# Ethernet.net
KiCad netlist of a schematic drawn in Altium Designer
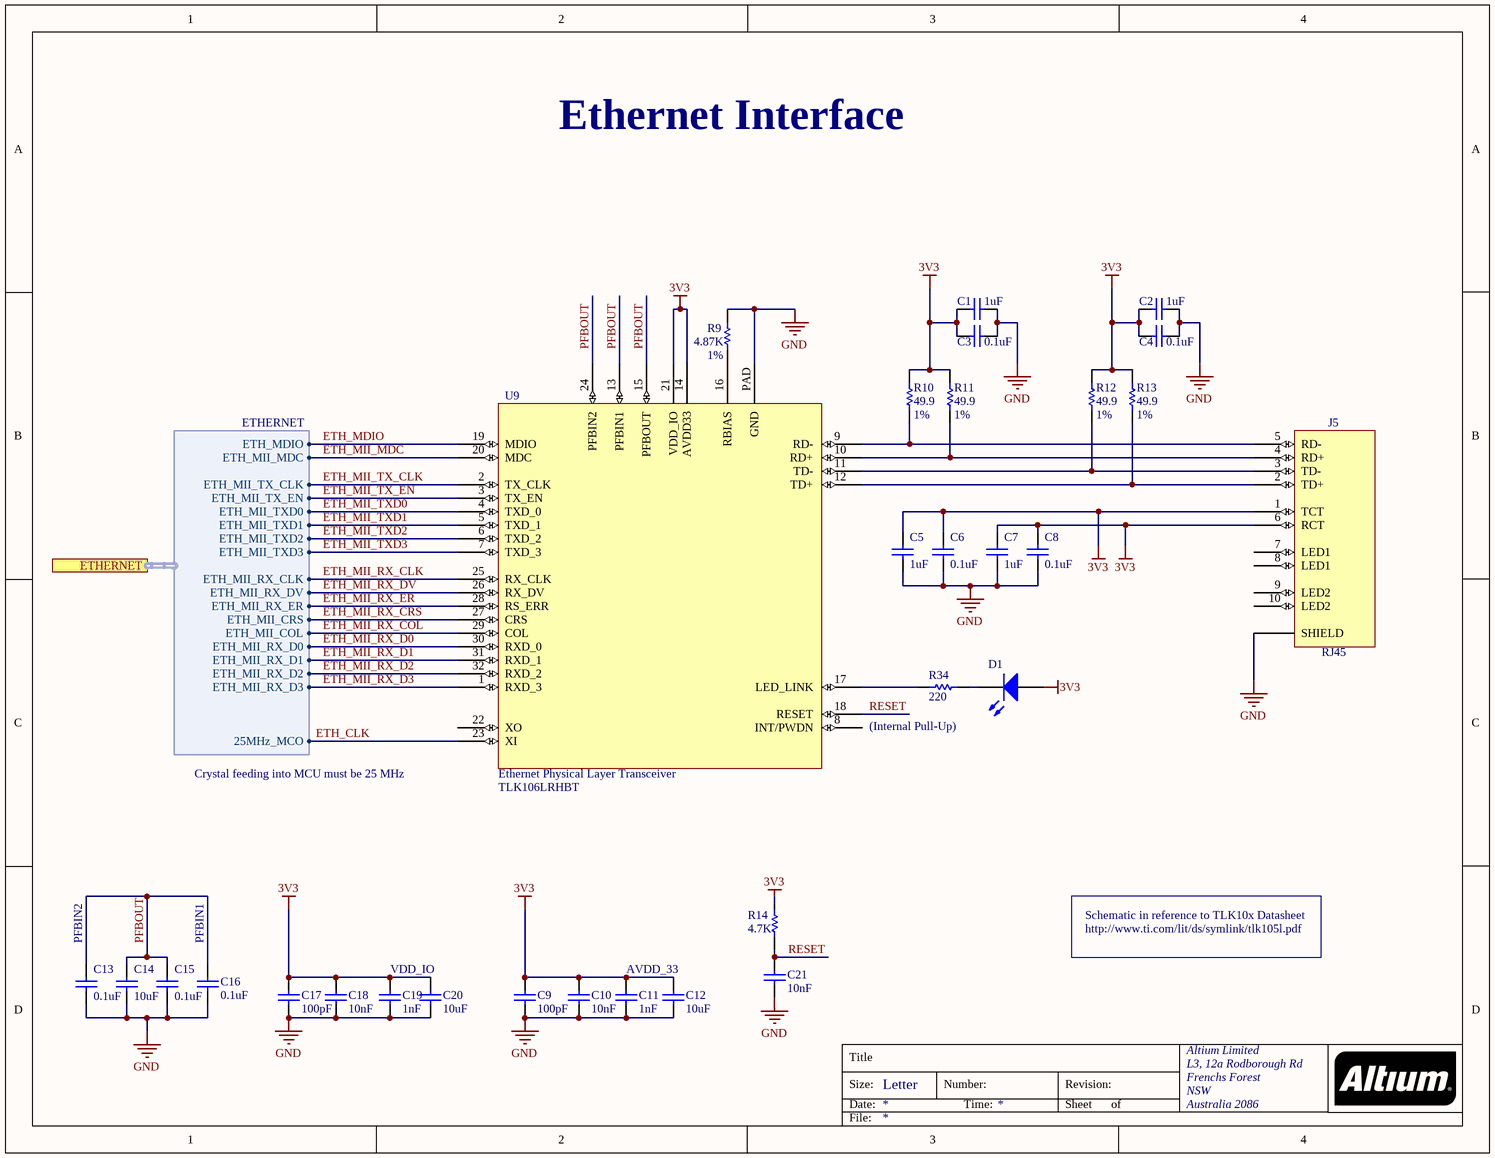
[diagram p0: Ethernet.SchDoc]

(export (version "E")
  (design (tool "Eeschema 10.0.6"))
  (components
    (comp (ref "C1")
      (value "1uF")
      (footprint "0402")
      (description "Capacitor")
      (fields (field (name "Comment") "Cap"))
      (libsource (lib "Miscellaneous Devices") (part "Cap"))
    )
    (comp (ref "C2")
      (value "1uF")
      (footprint "0402")
      (description "Capacitor")
      (fields (field (name "Comment") "Cap"))
      (libsource (lib "Miscellaneous Devices") (part "Cap"))
    )
    (comp (ref "C3")
      (value "0.1uF")
      (footprint "0402")
      (description "Capacitor")
      (fields (field (name "Comment") "Cap"))
      (libsource (lib "Miscellaneous Devices") (part "Cap"))
    )
    (comp (ref "C4")
      (value "0.1uF")
      (footprint "0402")
      (description "Capacitor")
      (fields (field (name "Comment") "Cap"))
      (libsource (lib "Miscellaneous Devices") (part "Cap"))
    )
    (comp (ref "C5")
      (value "1uF")
      (footprint "0402")
      (description "Capacitor")
      (fields (field (name "Comment") "Cap"))
      (libsource (lib "Miscellaneous Devices") (part "Cap"))
    )
    (comp (ref "C6")
      (value "0.1uF")
      (footprint "0402")
      (description "Capacitor")
      (fields (field (name "Comment") "Cap"))
      (libsource (lib "Miscellaneous Devices") (part "Cap"))
    )
    (comp (ref "C7")
      (value "1uF")
      (footprint "0402")
      (description "Capacitor")
      (fields (field (name "Comment") "Cap"))
      (libsource (lib "Miscellaneous Devices") (part "Cap"))
    )
    (comp (ref "C8")
      (value "0.1uF")
      (footprint "0402")
      (description "Capacitor")
      (fields (field (name "Comment") "Cap"))
      (libsource (lib "Miscellaneous Devices") (part "Cap"))
    )
    (comp (ref "C9")
      (value "100pF")
      (footprint "0402")
      (description "Capacitor (Semiconductor SIM Model)")
      (fields (field (name "Comment") "Cap Semi"))
      (libsource (lib "Miscellaneous Devices") (part "Cap Semi"))
    )
    (comp (ref "C10")
      (value "10nF")
      (footprint "0402")
      (description "Capacitor (Semiconductor SIM Model)")
      (fields (field (name "Comment") "Cap Semi"))
      (libsource (lib "Miscellaneous Devices") (part "Cap Semi"))
    )
    (comp (ref "C11")
      (value "1nF")
      (footprint "0402")
      (description "Capacitor (Semiconductor SIM Model)")
      (fields (field (name "Comment") "Cap Semi"))
      (libsource (lib "Miscellaneous Devices") (part "Cap Semi"))
    )
    (comp (ref "C12")
      (value "10uF")
      (footprint "0402")
      (description "Capacitor (Semiconductor SIM Model)")
      (fields (field (name "Comment") "Cap Semi"))
      (libsource (lib "Miscellaneous Devices") (part "Cap Semi"))
    )
    (comp (ref "C13")
      (value "0.1uF")
      (footprint "0402")
      (description "Capacitor (Semiconductor SIM Model)")
      (fields (field (name "Comment") "Cap Semi"))
      (libsource (lib "Miscellaneous Devices") (part "Cap Semi"))
    )
    (comp (ref "C14")
      (value "10uF")
      (footprint "0402")
      (description "Capacitor (Semiconductor SIM Model)")
      (fields (field (name "Comment") "Cap Semi"))
      (libsource (lib "Miscellaneous Devices") (part "Cap Semi"))
    )
    (comp (ref "C15")
      (value "0.1uF")
      (footprint "0402")
      (description "Capacitor (Semiconductor SIM Model)")
      (fields (field (name "Comment") "Cap Semi"))
      (libsource (lib "Miscellaneous Devices") (part "Cap Semi"))
    )
    (comp (ref "C16")
      (value "0.1uF")
      (footprint "0402")
      (description "Capacitor (Semiconductor SIM Model)")
      (fields (field (name "Comment") "Cap Semi"))
      (libsource (lib "Miscellaneous Devices") (part "Cap Semi"))
    )
    (comp (ref "C17")
      (value "100pF")
      (footprint "0402")
      (description "Capacitor (Semiconductor SIM Model)")
      (fields (field (name "Comment") "Cap Semi"))
      (libsource (lib "Miscellaneous Devices") (part "Cap Semi"))
    )
    (comp (ref "C18")
      (value "10nF")
      (footprint "0402")
      (description "Capacitor (Semiconductor SIM Model)")
      (fields (field (name "Comment") "Cap Semi"))
      (libsource (lib "Miscellaneous Devices") (part "Cap Semi"))
    )
    (comp (ref "C19")
      (value "1nF")
      (footprint "0402")
      (description "Capacitor (Semiconductor SIM Model)")
      (fields (field (name "Comment") "Cap Semi"))
      (libsource (lib "Miscellaneous Devices") (part "Cap Semi"))
    )
    (comp (ref "C20")
      (value "10uF")
      (footprint "0402")
      (description "Capacitor (Semiconductor SIM Model)")
      (fields (field (name "Comment") "Cap Semi"))
      (libsource (lib "Miscellaneous Devices") (part "Cap Semi"))
    )
    (comp (ref "C21")
      (value "10nF")
      (footprint "0402")
      (description "Capacitor (Semiconductor SIM Model)")
      (fields (field (name "Comment") "Cap Semi"))
      (libsource (lib "Miscellaneous Devices") (part "Cap Semi"))
    )
    (comp (ref "D1")
      (value "LED3")
      (footprint "0402")
      (description "Typical BLUE SiC LED")
      (fields (field (name "DIGIKEY PART NO") "754-1105-1-ND") (field (name "MNF PART NO") "APHHS1005SYCK"))
      (libsource (lib "Miscellaneous Devices") (part "LED3"))
    )
    (comp (ref "J5")
      (value "RJ45")
      (footprint "RJ45")
      (description "Ethernet Jack with Magnetics")
      (fields
        (field (name "DIGIKEY PART NUMBER") "507-1444-ND")
        (field (name "MANUFACTURER PART NUMBER") "08B0-1X1T-03-F")
      )
      (libsource (lib "LaunchyRIOComponents") (part "RJ45 Jack with Magnetics"))
    )
    (comp (ref "R9")
      (value "4.87K")
      (footprint "0402")
      (description "Resistor")
      (fields (field (name "TOLERANCE") "1%") (field (name "Comment") "Res1"))
      (libsource (lib "Miscellaneous Devices") (part "Res1"))
    )
    (comp (ref "R10")
      (value "49.9")
      (footprint "0402")
      (description "Resistor")
      (fields (field (name "TOLERANCE") "1%") (field (name "Comment") "Res1"))
      (libsource (lib "Miscellaneous Devices") (part "Res1"))
    )
    (comp (ref "R11")
      (value "49.9")
      (footprint "0402")
      (description "Resistor")
      (fields (field (name "TOLERANCE") "1%") (field (name "Comment") "Res1"))
      (libsource (lib "Miscellaneous Devices") (part "Res1"))
    )
    (comp (ref "R12")
      (value "49.9")
      (footprint "0402")
      (description "Resistor")
      (fields (field (name "TOLERANCE") "1%") (field (name "Comment") "Res1"))
      (libsource (lib "Miscellaneous Devices") (part "Res1"))
    )
    (comp (ref "R13")
      (value "49.9")
      (footprint "0402")
      (description "Resistor")
      (fields (field (name "TOLERANCE") "1%") (field (name "Comment") "Res1"))
      (libsource (lib "Miscellaneous Devices") (part "Res1"))
    )
    (comp (ref "R14")
      (value "4.7K")
      (footprint "0402")
      (description "Resistor")
      (fields (field (name "Comment") "Res1"))
      (libsource (lib "Miscellaneous Devices") (part "Res1"))
    )
    (comp (ref "R34")
      (value "220")
      (footprint "0402")
      (description "Resistor")
      (fields (field (name "Comment") "Res1"))
      (libsource (lib "Miscellaneous Devices") (part "Res1"))
    )
    (comp (ref "U9")
      (value "Ethernet Physical Layer Transceiver")
      (footprint "VQFN32-PHY-TRANSCEIVER")
      (fields
        (field (name "BASE PART NUMBER") "TLK106")
        (field (name "DIGIKEY PART NUMBER") "296-39585-2-ND")
        (field (name "MANUFACTURER PART NUMBER") "TLK106LRHBT")
      )
      (libsource (lib "LaunchyRIOComponents") (part "TLK106LRHBT"))
    )
  )
  (nets
    (net (code "2") (name "/ETH_CLK") (class "Default")
      (node (ref "U9") (pin "23") (pinfunction "XI_23") (pintype "bidirectional"))
    )
    (net (code "3") (name "/ETH_MDIO") (class "Default")
      (node (ref "U9") (pin "19") (pinfunction "MDIO_19") (pintype "bidirectional"))
    )
    (net (code "4") (name "/ETH_MII_MDC") (class "Default")
      (node (ref "U9") (pin "20") (pinfunction "MDC_20") (pintype "bidirectional"))
    )
    (net (code "5") (name "/ETH_MII_RX_CLK") (class "Default")
      (node (ref "U9") (pin "25") (pinfunction "RX_CLK_25") (pintype "bidirectional"))
    )
    (net (code "6") (name "/ETH_MII_RX_COL") (class "Default")
      (node (ref "U9") (pin "29") (pinfunction "COL_29") (pintype "bidirectional"))
    )
    (net (code "7") (name "/ETH_MII_RX_CRS") (class "Default")
      (node (ref "U9") (pin "27") (pinfunction "CRS_27") (pintype "bidirectional"))
    )
    (net (code "8") (name "/ETH_MII_RX_D0") (class "Default")
      (node (ref "U9") (pin "30") (pinfunction "RXD_0_30") (pintype "bidirectional"))
    )
    (net (code "9") (name "/ETH_MII_RX_D1") (class "Default")
      (node (ref "U9") (pin "31") (pinfunction "RXD_1_31") (pintype "bidirectional"))
    )
    (net (code "10") (name "/ETH_MII_RX_D2") (class "Default")
      (node (ref "U9") (pin "32") (pinfunction "RXD_2_32") (pintype "bidirectional"))
    )
    (net (code "11") (name "/ETH_MII_RX_D3") (class "Default")
      (node (ref "U9") (pin "1") (pinfunction "RXD_3_1") (pintype "bidirectional"))
    )
    (net (code "12") (name "/ETH_MII_RX_DV") (class "Default")
      (node (ref "U9") (pin "26") (pinfunction "RX_DV_26") (pintype "bidirectional"))
    )
    (net (code "13") (name "/ETH_MII_RX_ER") (class "Default")
      (node (ref "U9") (pin "28") (pinfunction "RS_ERR_28") (pintype "bidirectional"))
    )
    (net (code "14") (name "/ETH_MII_TXD0") (class "Default")
      (node (ref "U9") (pin "4") (pinfunction "TXD_0_4") (pintype "bidirectional"))
    )
    (net (code "15") (name "/ETH_MII_TXD1") (class "Default")
      (node (ref "U9") (pin "5") (pinfunction "TXD_1_5") (pintype "bidirectional"))
    )
    (net (code "16") (name "/ETH_MII_TXD2") (class "Default")
      (node (ref "U9") (pin "6") (pinfunction "TXD_2_6") (pintype "bidirectional"))
    )
    (net (code "17") (name "/ETH_MII_TXD3") (class "Default")
      (node (ref "U9") (pin "7") (pinfunction "TXD_3_7") (pintype "bidirectional"))
    )
    (net (code "18") (name "/ETH_MII_TX_CLK") (class "Default")
      (node (ref "U9") (pin "2") (pinfunction "TX_CLK_2") (pintype "bidirectional"))
    )
    (net (code "19") (name "/ETH_MII_TX_EN") (class "Default")
      (node (ref "U9") (pin "3") (pinfunction "TX_EN_3") (pintype "bidirectional"))
    )
    (net (code "20") (name "/PFBOUT") (class "Default")
      (node (ref "C13") (pin "2") (pinfunction "2_2") (pintype "passive"))
      (node (ref "C14") (pin "2") (pinfunction "2_2") (pintype "passive"))
      (node (ref "C15") (pin "2") (pinfunction "2_2") (pintype "passive"))
      (node (ref "C16") (pin "2") (pinfunction "2_2") (pintype "passive"))
      (node (ref "U9") (pin "13") (pinfunction "PFBIN1_13") (pintype "bidirectional"))
      (node (ref "U9") (pin "15") (pinfunction "PFBOUT_15") (pintype "bidirectional"))
      (node (ref "U9") (pin "24") (pinfunction "PFBIN2_24") (pintype "bidirectional"))
    )
    (net (code "21") (name "/RESET") (class "Default")
      (node (ref "C21") (pin "2") (pinfunction "2_2") (pintype "passive"))
      (node (ref "R14") (pin "1") (pinfunction "1_1") (pintype "passive"))
      (node (ref "U9") (pin "18") (pinfunction "RESET_18") (pintype "bidirectional"))
    )
    (net (code "23") (name "3V3") (class "Default")
      (node (ref "C1") (pin "2") (pinfunction "2_2") (pintype "passive"))
      (node (ref "C10") (pin "2") (pinfunction "2_2") (pintype "passive"))
      (node (ref "C11") (pin "2") (pinfunction "2_2") (pintype "passive"))
      (node (ref "C12") (pin "2") (pinfunction "2_2") (pintype "passive"))
      (node (ref "C17") (pin "2") (pinfunction "2_2") (pintype "passive"))
      (node (ref "C18") (pin "2") (pinfunction "2_2") (pintype "passive"))
      (node (ref "C19") (pin "2") (pinfunction "2_2") (pintype "passive"))
      (node (ref "C2") (pin "2") (pinfunction "2_2") (pintype "passive"))
      (node (ref "C20") (pin "2") (pinfunction "2_2") (pintype "passive"))
      (node (ref "C3") (pin "2") (pinfunction "2_2") (pintype "passive"))
      (node (ref "C4") (pin "2") (pinfunction "2_2") (pintype "passive"))
      (node (ref "C5") (pin "1") (pinfunction "1_1") (pintype "passive"))
      (node (ref "C6") (pin "1") (pinfunction "1_1") (pintype "passive"))
      (node (ref "C7") (pin "1") (pinfunction "1_1") (pintype "passive"))
      (node (ref "C8") (pin "1") (pinfunction "1_1") (pintype "passive"))
      (node (ref "C9") (pin "2") (pinfunction "2_2") (pintype "passive"))
      (node (ref "D1") (pin "1") (pinfunction "A_1") (pintype "passive"))
      (node (ref "J5") (pin "1") (pinfunction "TCT_1") (pintype "bidirectional"))
      (node (ref "J5") (pin "6") (pinfunction "RCT_6") (pintype "bidirectional"))
      (node (ref "R10") (pin "2") (pinfunction "2_2") (pintype "passive"))
      (node (ref "R11") (pin "2") (pinfunction "2_2") (pintype "passive"))
      (node (ref "R12") (pin "2") (pinfunction "2_2") (pintype "passive"))
      (node (ref "R13") (pin "2") (pinfunction "2_2") (pintype "passive"))
      (node (ref "R14") (pin "2") (pinfunction "2_2") (pintype "passive"))
      (node (ref "U9") (pin "14") (pinfunction "AVDD33_14") (pintype "power_in"))
      (node (ref "U9") (pin "21") (pinfunction "VDD_IO_21") (pintype "power_in"))
    )
    (net (code "24") (name "GND") (class "Default")
      (node (ref "C1") (pin "1") (pinfunction "1_1") (pintype "passive"))
      (node (ref "C10") (pin "1") (pinfunction "1_1") (pintype "passive"))
      (node (ref "C11") (pin "1") (pinfunction "1_1") (pintype "passive"))
      (node (ref "C12") (pin "1") (pinfunction "1_1") (pintype "passive"))
      (node (ref "C13") (pin "1") (pinfunction "1_1") (pintype "passive"))
      (node (ref "C14") (pin "1") (pinfunction "1_1") (pintype "passive"))
      (node (ref "C15") (pin "1") (pinfunction "1_1") (pintype "passive"))
      (node (ref "C16") (pin "1") (pinfunction "1_1") (pintype "passive"))
      (node (ref "C17") (pin "1") (pinfunction "1_1") (pintype "passive"))
      (node (ref "C18") (pin "1") (pinfunction "1_1") (pintype "passive"))
      (node (ref "C19") (pin "1") (pinfunction "1_1") (pintype "passive"))
      (node (ref "C2") (pin "1") (pinfunction "1_1") (pintype "passive"))
      (node (ref "C20") (pin "1") (pinfunction "1_1") (pintype "passive"))
      (node (ref "C21") (pin "1") (pinfunction "1_1") (pintype "passive"))
      (node (ref "C3") (pin "1") (pinfunction "1_1") (pintype "passive"))
      (node (ref "C4") (pin "1") (pinfunction "1_1") (pintype "passive"))
      (node (ref "C5") (pin "2") (pinfunction "2_2") (pintype "passive"))
      (node (ref "C6") (pin "2") (pinfunction "2_2") (pintype "passive"))
      (node (ref "C7") (pin "2") (pinfunction "2_2") (pintype "passive"))
      (node (ref "C8") (pin "2") (pinfunction "2_2") (pintype "passive"))
      (node (ref "C9") (pin "1") (pinfunction "1_1") (pintype "passive"))
      (node (ref "J5") (pin "SHIELD") (pinfunction "SHIELD_SHIELD") (pintype "passive"))
      (node (ref "R9") (pin "2") (pinfunction "2_2") (pintype "passive"))
      (node (ref "U9") (pin "PAD") (pinfunction "GND_PAD") (pintype "passive"))
    )
    (net (code "25") (name "Net-(D1-K)") (class "Default")
      (node (ref "D1") (pin "2") (pinfunction "K_2") (pintype "passive"))
      (node (ref "R34") (pin "2") (pinfunction "2_2") (pintype "passive"))
    )
    (net (code "26") (name "Net-(J5-RD+)") (class "Default")
      (node (ref "J5") (pin "4") (pinfunction "RD+_4") (pintype "bidirectional"))
      (node (ref "R11") (pin "1") (pinfunction "1_1") (pintype "passive"))
      (node (ref "U9") (pin "10") (pinfunction "RD+_10") (pintype "bidirectional"))
    )
    (net (code "27") (name "Net-(J5-RD-)") (class "Default")
      (node (ref "J5") (pin "5") (pinfunction "RD-_5") (pintype "bidirectional"))
      (node (ref "R10") (pin "1") (pinfunction "1_1") (pintype "passive"))
      (node (ref "U9") (pin "9") (pinfunction "RD-_9") (pintype "bidirectional"))
    )
    (net (code "28") (name "Net-(J5-TD+)") (class "Default")
      (node (ref "J5") (pin "2") (pinfunction "TD+_2") (pintype "bidirectional"))
      (node (ref "R13") (pin "1") (pinfunction "1_1") (pintype "passive"))
      (node (ref "U9") (pin "12") (pinfunction "TD+_12") (pintype "bidirectional"))
    )
    (net (code "29") (name "Net-(J5-TD-)") (class "Default")
      (node (ref "J5") (pin "3") (pinfunction "TD-_3") (pintype "bidirectional"))
      (node (ref "R12") (pin "1") (pinfunction "1_1") (pintype "passive"))
      (node (ref "U9") (pin "11") (pinfunction "TD-_11") (pintype "bidirectional"))
    )
    (net (code "30") (name "Net-(U9-LED_LINK)") (class "Default")
      (node (ref "R34") (pin "1") (pinfunction "1_1") (pintype "passive"))
      (node (ref "U9") (pin "17") (pinfunction "LED_LINK_17") (pintype "bidirectional"))
    )
    (net (code "31") (name "Net-(U9-RBIAS)") (class "Default")
      (node (ref "R9") (pin "1") (pinfunction "1_1") (pintype "passive"))
      (node (ref "U9") (pin "16") (pinfunction "RBIAS_16") (pintype "power_in"))
    )
    (net (code "32") (name "unconnected-(J5-LED1-Pad7)") (class "Default")
      (node (ref "J5") (pin "7") (pinfunction "LED1_7") (pintype "bidirectional"))
    )
    (net (code "33") (name "unconnected-(J5-LED1-Pad8)") (class "Default")
      (node (ref "J5") (pin "8") (pinfunction "LED1_8") (pintype "bidirectional"))
    )
    (net (code "34") (name "unconnected-(J5-LED2-Pad9)") (class "Default")
      (node (ref "J5") (pin "9") (pinfunction "LED2_9") (pintype "bidirectional"))
    )
    (net (code "35") (name "unconnected-(J5-LED2-Pad10)") (class "Default")
      (node (ref "J5") (pin "10") (pinfunction "LED2_10") (pintype "bidirectional"))
    )
    (net (code "36") (name "unconnected-(U9-INT{slash}PWDN-Pad8)") (class "Default")
      (node (ref "U9") (pin "8") (pinfunction "INT/PWDN_8") (pintype "bidirectional"))
    )
    (net (code "37") (name "unconnected-(U9-XO-Pad22)") (class "Default")
      (node (ref "U9") (pin "22") (pinfunction "XO_22") (pintype "bidirectional"))
    )
  )
)
